# routed_anemo3.net
KiCad netlist of a schematic drawn in EAGLE
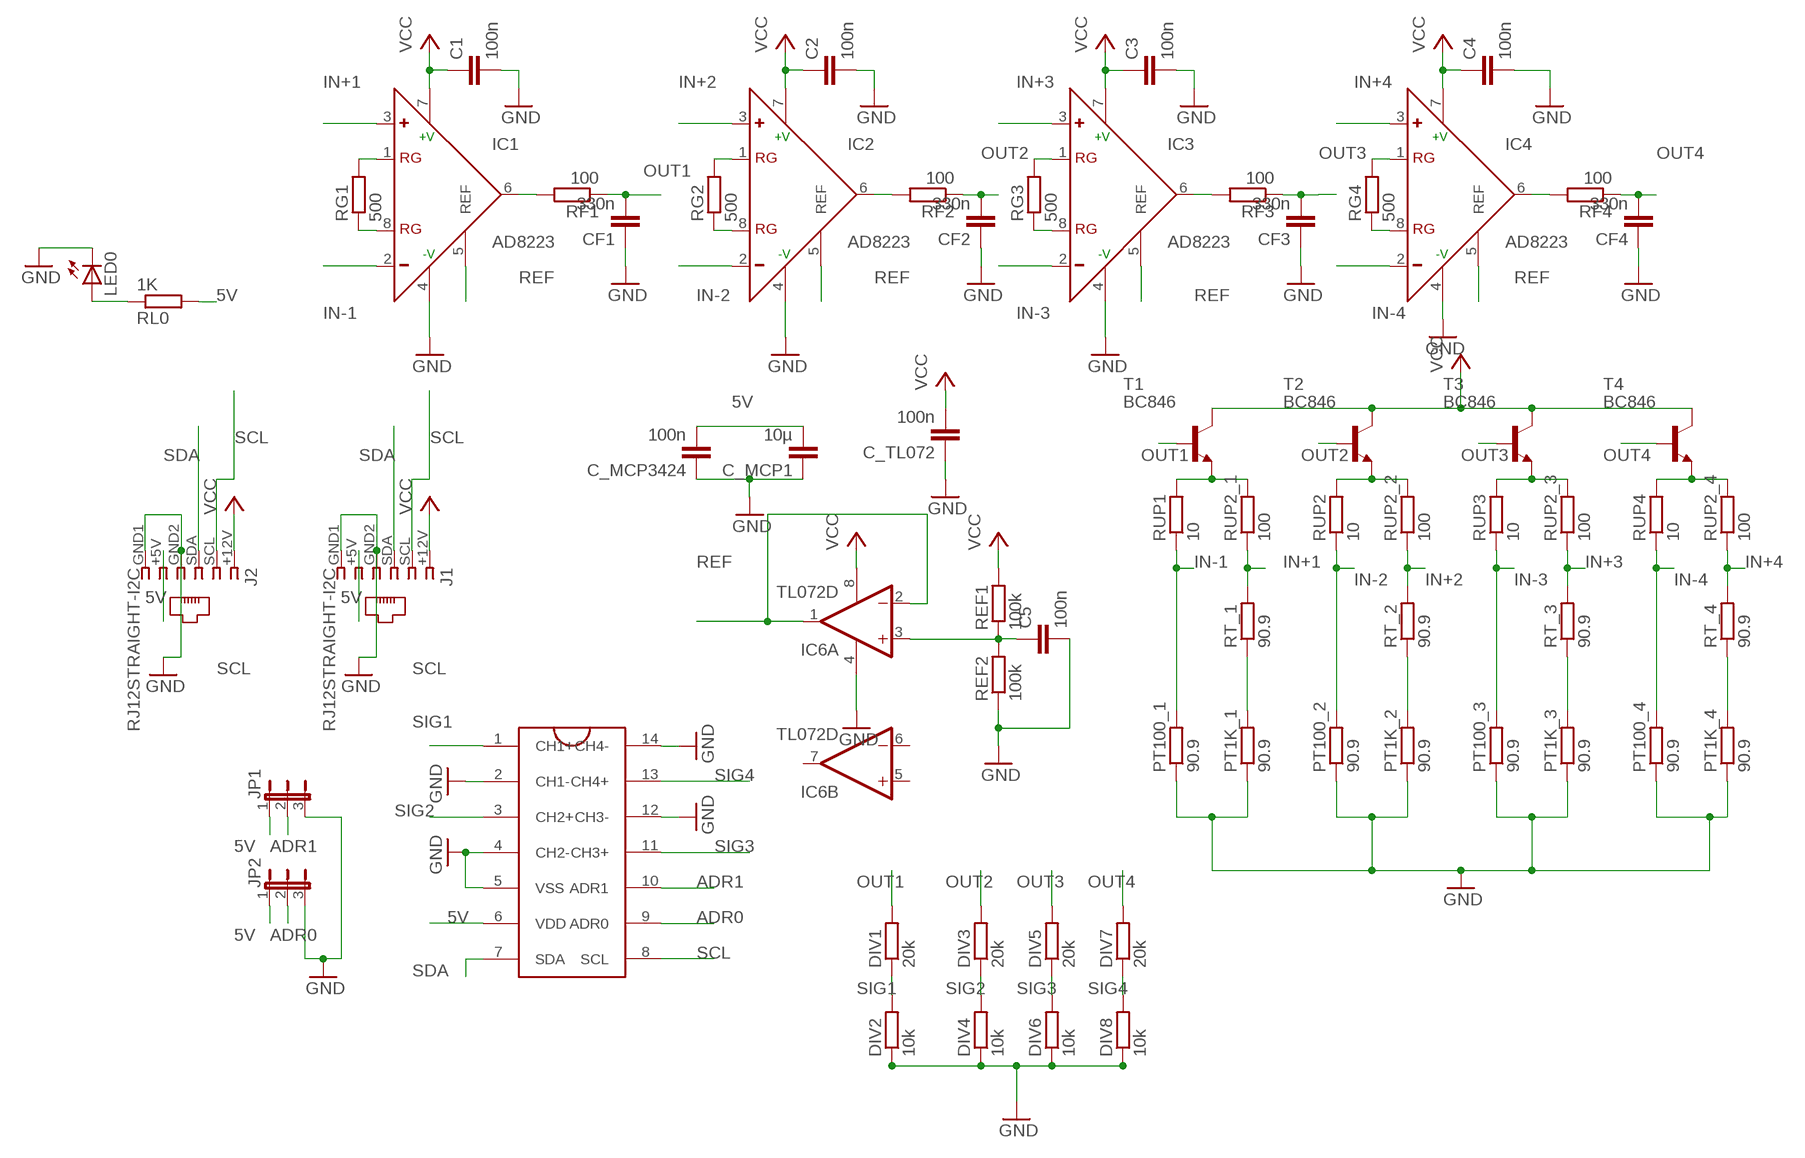
[diagram p0: schematic, sheet 1]

(export (version "E")
  (design (tool "Eeschema 10.0.6"))
  (components
    (comp (ref "C1")
      (value "100n")
      (footprint "eagle-import:C1206")
      (libsource (lib "eagle-import") (part "C-EUC1206"))
    )
    (comp (ref "C2")
      (value "100n")
      (footprint "eagle-import:C1206")
      (libsource (lib "eagle-import") (part "C-EUC1206"))
    )
    (comp (ref "C3")
      (value "100n")
      (footprint "eagle-import:C1206")
      (libsource (lib "eagle-import") (part "C-EUC1206"))
    )
    (comp (ref "C4")
      (value "100n")
      (footprint "eagle-import:C1206")
      (libsource (lib "eagle-import") (part "C-EUC1206"))
    )
    (comp (ref "C5")
      (value "100n")
      (footprint "eagle-import:C1206")
      (libsource (lib "eagle-import") (part "C-EUC1206"))
    )
    (comp (ref "CF1")
      (value "330n")
      (footprint "eagle-import:C1206")
      (libsource (lib "eagle-import") (part "C-EUC1206"))
    )
    (comp (ref "CF2")
      (value "330n")
      (footprint "eagle-import:C1206")
      (libsource (lib "eagle-import") (part "C-EUC1206"))
    )
    (comp (ref "CF3")
      (value "330n")
      (footprint "eagle-import:C1206")
      (libsource (lib "eagle-import") (part "C-EUC1206"))
    )
    (comp (ref "CF4")
      (value "330n")
      (footprint "eagle-import:C1206")
      (libsource (lib "eagle-import") (part "C-EUC1206"))
    )
    (comp (ref "C_MCP1")
      (value "10µ")
      (footprint "eagle-import:C1206")
      (libsource (lib "eagle-import") (part "C-EUC1206"))
    )
    (comp (ref "C_MCP3424")
      (value "100n")
      (footprint "eagle-import:C1206")
      (libsource (lib "eagle-import") (part "C-EUC1206"))
    )
    (comp (ref "C_TL072")
      (value "100n")
      (footprint "eagle-import:C1206")
      (libsource (lib "eagle-import") (part "C-EUC1206"))
    )
    (comp (ref "DIV1")
      (value "20k")
      (footprint "eagle-import:M1206")
      (libsource (lib "eagle-import") (part "R-EU_M1206"))
    )
    (comp (ref "DIV2")
      (value "10k")
      (footprint "eagle-import:M1206")
      (libsource (lib "eagle-import") (part "R-EU_M1206"))
    )
    (comp (ref "DIV3")
      (value "20k")
      (footprint "eagle-import:M1206")
      (libsource (lib "eagle-import") (part "R-EU_M1206"))
    )
    (comp (ref "DIV4")
      (value "10k")
      (footprint "eagle-import:M1206")
      (libsource (lib "eagle-import") (part "R-EU_M1206"))
    )
    (comp (ref "DIV5")
      (value "20k")
      (footprint "eagle-import:M1206")
      (libsource (lib "eagle-import") (part "R-EU_M1206"))
    )
    (comp (ref "DIV6")
      (value "10k")
      (footprint "eagle-import:M1206")
      (libsource (lib "eagle-import") (part "R-EU_M1206"))
    )
    (comp (ref "DIV7")
      (value "20k")
      (footprint "eagle-import:M1206")
      (libsource (lib "eagle-import") (part "R-EU_M1206"))
    )
    (comp (ref "DIV8")
      (value "10k")
      (footprint "eagle-import:M1206")
      (libsource (lib "eagle-import") (part "R-EU_M1206"))
    )
    (comp (ref "IC1")
      (value "AD8223")
      (footprint "eagle-import:SO8")
      (fields (field (name "MPN") "AD620AR"))
      (libsource (lib "eagle-import") (part "AD620R"))
    )
    (comp (ref "IC2")
      (value "AD8223")
      (footprint "eagle-import:SO8")
      (fields (field (name "MPN") "AD620AR"))
      (libsource (lib "eagle-import") (part "AD620R"))
    )
    (comp (ref "IC3")
      (value "AD8223")
      (footprint "eagle-import:SO8")
      (fields (field (name "MPN") "AD620AR"))
      (libsource (lib "eagle-import") (part "AD620R"))
    )
    (comp (ref "IC4")
      (value "AD8223")
      (footprint "eagle-import:SO8")
      (fields (field (name "MPN") "AD620AR"))
      (libsource (lib "eagle-import") (part "AD620R"))
    )
    (comp (ref "IC6")
      (value "TL072D")
      (footprint "eagle-import:SO08")
      (libsource (lib "eagle-import") (part "TL072D"))
    )
    (comp (ref "J1")
      (value "RJ12STRAIGHT-I2C")
      (footprint "eagle-import:RJ12-STRAIGHT-I2C")
      (libsource (lib "eagle-import") (part "RJ12STRAIGHT-I2C"))
    )
    (comp (ref "J2")
      (value "RJ12STRAIGHT-I2C")
      (footprint "eagle-import:RJ12-STRAIGHT-I2C")
      (libsource (lib "eagle-import") (part "RJ12STRAIGHT-I2C"))
    )
    (comp (ref "JP1")
      (value "JP2E")
      (footprint "eagle-import:JP2")
      (libsource (lib "eagle-import") (part "JP2E"))
    )
    (comp (ref "JP2")
      (value "JP2E")
      (footprint "eagle-import:JP2")
      (libsource (lib "eagle-import") (part "JP2E"))
    )
    (comp (ref "LED0")
      (value "LED1206")
      (footprint "eagle-import:LED-1206")
      (libsource (lib "eagle-import") (part "LED1206"))
    )
    (comp (ref "PT1K_1")
      (value "90.9")
      (footprint "eagle-import:M1206")
      (libsource (lib "eagle-import") (part "R-EU_M1206"))
    )
    (comp (ref "PT1K_2")
      (value "90.9")
      (footprint "eagle-import:M1206")
      (libsource (lib "eagle-import") (part "R-EU_M1206"))
    )
    (comp (ref "PT1K_3")
      (value "90.9")
      (footprint "eagle-import:M1206")
      (libsource (lib "eagle-import") (part "R-EU_M1206"))
    )
    (comp (ref "PT1K_4")
      (value "90.9")
      (footprint "eagle-import:M1206")
      (libsource (lib "eagle-import") (part "R-EU_M1206"))
    )
    (comp (ref "PT100_1")
      (value "90.9")
      (footprint "eagle-import:M1206")
      (libsource (lib "eagle-import") (part "R-EU_M1206"))
    )
    (comp (ref "PT100_2")
      (value "90.9")
      (footprint "eagle-import:M1206")
      (libsource (lib "eagle-import") (part "R-EU_M1206"))
    )
    (comp (ref "PT100_3")
      (value "90.9")
      (footprint "eagle-import:M1206")
      (libsource (lib "eagle-import") (part "R-EU_M1206"))
    )
    (comp (ref "PT100_4")
      (value "90.9")
      (footprint "eagle-import:M1206")
      (libsource (lib "eagle-import") (part "R-EU_M1206"))
    )
    (comp (ref "REF1")
      (value "100k")
      (footprint "eagle-import:M1206")
      (libsource (lib "eagle-import") (part "R-EU_M1206"))
    )
    (comp (ref "REF2")
      (value "100k")
      (footprint "eagle-import:M1206")
      (libsource (lib "eagle-import") (part "R-EU_M1206"))
    )
    (comp (ref "RF1")
      (value "100")
      (footprint "eagle-import:M1206")
      (libsource (lib "eagle-import") (part "R-EU_M1206"))
    )
    (comp (ref "RF2")
      (value "100")
      (footprint "eagle-import:M1206")
      (libsource (lib "eagle-import") (part "R-EU_M1206"))
    )
    (comp (ref "RF3")
      (value "100")
      (footprint "eagle-import:M1206")
      (libsource (lib "eagle-import") (part "R-EU_M1206"))
    )
    (comp (ref "RF4")
      (value "100")
      (footprint "eagle-import:M1206")
      (libsource (lib "eagle-import") (part "R-EU_M1206"))
    )
    (comp (ref "RG1")
      (value "500")
      (footprint "eagle-import:M1206")
      (libsource (lib "eagle-import") (part "R-EU_M1206"))
    )
    (comp (ref "RG2")
      (value "500")
      (footprint "eagle-import:M1206")
      (libsource (lib "eagle-import") (part "R-EU_M1206"))
    )
    (comp (ref "RG3")
      (value "500")
      (footprint "eagle-import:M1206")
      (libsource (lib "eagle-import") (part "R-EU_M1206"))
    )
    (comp (ref "RG4")
      (value "500")
      (footprint "eagle-import:M1206")
      (libsource (lib "eagle-import") (part "R-EU_M1206"))
    )
    (comp (ref "RL0")
      (value "1K")
      (footprint "eagle-import:M1206")
      (libsource (lib "eagle-import") (part "R-EU_M1206"))
    )
    (comp (ref "RT_1")
      (value "90.9")
      (footprint "eagle-import:M1206")
      (libsource (lib "eagle-import") (part "R-EU_M1206"))
    )
    (comp (ref "RT_2")
      (value "90.9")
      (footprint "eagle-import:M1206")
      (libsource (lib "eagle-import") (part "R-EU_M1206"))
    )
    (comp (ref "RT_3")
      (value "90.9")
      (footprint "eagle-import:M1206")
      (libsource (lib "eagle-import") (part "R-EU_M1206"))
    )
    (comp (ref "RT_4")
      (value "90.9")
      (footprint "eagle-import:M1206")
      (libsource (lib "eagle-import") (part "R-EU_M1206"))
    )
    (comp (ref "RUP1")
      (value "10")
      (footprint "eagle-import:M1206")
      (libsource (lib "eagle-import") (part "R-EU_M1206"))
    )
    (comp (ref "RUP2")
      (value "10")
      (footprint "eagle-import:M1206")
      (libsource (lib "eagle-import") (part "R-EU_M1206"))
    )
    (comp (ref "RUP2_1")
      (value "100")
      (footprint "eagle-import:M1206")
      (libsource (lib "eagle-import") (part "R-EU_M1206"))
    )
    (comp (ref "RUP2_2")
      (value "100")
      (footprint "eagle-import:M1206")
      (libsource (lib "eagle-import") (part "R-EU_M1206"))
    )
    (comp (ref "RUP2_3")
      (value "100")
      (footprint "eagle-import:M1206")
      (libsource (lib "eagle-import") (part "R-EU_M1206"))
    )
    (comp (ref "RUP2_4")
      (value "100")
      (footprint "eagle-import:M1206")
      (libsource (lib "eagle-import") (part "R-EU_M1206"))
    )
    (comp (ref "RUP3")
      (value "10")
      (footprint "eagle-import:M1206")
      (libsource (lib "eagle-import") (part "R-EU_M1206"))
    )
    (comp (ref "RUP4")
      (value "10")
      (footprint "eagle-import:M1206")
      (libsource (lib "eagle-import") (part "R-EU_M1206"))
    )
    (comp (ref "T1")
      (value "BC846")
      (footprint "eagle-import:SOT23")
      (libsource (lib "eagle-import") (part "BC846"))
    )
    (comp (ref "T2")
      (value "BC846")
      (footprint "eagle-import:SOT23")
      (libsource (lib "eagle-import") (part "BC846"))
    )
    (comp (ref "T3")
      (value "BC846")
      (footprint "eagle-import:SOT23")
      (libsource (lib "eagle-import") (part "BC846"))
    )
    (comp (ref "T4")
      (value "BC846")
      (footprint "eagle-import:SOT23")
      (libsource (lib "eagle-import") (part "BC846"))
    )
    (comp (ref "U$1")
      (value "MCP3424(SO14)")
      (footprint "eagle-import:14LDSOIC")
      (libsource (lib "eagle-import") (part "MCP3424(SO14)"))
    )
  )
  (nets
    (net (code "1") (name "/5V") (class "Default")
      (node (ref "C_MCP1") (pin "2") (pinfunction "2_2") (pintype "passive"))
      (node (ref "C_MCP3424") (pin "2") (pinfunction "2_2") (pintype "passive"))
      (node (ref "J1") (pin "+5V") (pinfunction "5_+5V") (pintype "bidirectional"))
      (node (ref "J2") (pin "+5V") (pinfunction "5_+5V") (pintype "bidirectional"))
      (node (ref "JP1") (pin "1") (pinfunction "1_1") (pintype "passive"))
      (node (ref "JP2") (pin "1") (pinfunction "1_1") (pintype "passive"))
      (node (ref "RL0") (pin "2") (pinfunction "2_2") (pintype "passive"))
      (node (ref "U$1") (pin "6") (pinfunction "VDD_6") (pintype "bidirectional"))
    )
    (net (code "2") (name "/ADR0") (class "Default")
      (node (ref "JP2") (pin "2") (pinfunction "2_2") (pintype "passive"))
      (node (ref "U$1") (pin "9") (pinfunction "ADR0_9") (pintype "bidirectional"))
    )
    (net (code "3") (name "/ADR1") (class "Default")
      (node (ref "JP1") (pin "2") (pinfunction "2_2") (pintype "passive"))
      (node (ref "U$1") (pin "10") (pinfunction "ADR1_10") (pintype "bidirectional"))
    )
    (net (code "4") (name "/IN+1") (class "Default")
      (node (ref "IC1") (pin "3") (pinfunction "+_3") (pintype "input"))
      (node (ref "RT_1") (pin "2") (pinfunction "2_2") (pintype "passive"))
      (node (ref "RUP2_1") (pin "1") (pinfunction "1_1") (pintype "passive"))
    )
    (net (code "5") (name "/IN+2") (class "Default")
      (node (ref "IC2") (pin "3") (pinfunction "+_3") (pintype "input"))
      (node (ref "RT_2") (pin "2") (pinfunction "2_2") (pintype "passive"))
      (node (ref "RUP2_2") (pin "1") (pinfunction "1_1") (pintype "passive"))
    )
    (net (code "6") (name "/IN+3") (class "Default")
      (node (ref "IC3") (pin "3") (pinfunction "+_3") (pintype "input"))
      (node (ref "RT_3") (pin "2") (pinfunction "2_2") (pintype "passive"))
      (node (ref "RUP2_3") (pin "1") (pinfunction "1_1") (pintype "passive"))
    )
    (net (code "7") (name "/IN+4") (class "Default")
      (node (ref "IC4") (pin "3") (pinfunction "+_3") (pintype "input"))
      (node (ref "RT_4") (pin "2") (pinfunction "2_2") (pintype "passive"))
      (node (ref "RUP2_4") (pin "1") (pinfunction "1_1") (pintype "passive"))
    )
    (net (code "8") (name "/IN-1") (class "Default")
      (node (ref "IC1") (pin "2") (pinfunction "-_2") (pintype "input"))
      (node (ref "PT100_1") (pin "2") (pinfunction "2_2") (pintype "passive"))
      (node (ref "RUP1") (pin "1") (pinfunction "1_1") (pintype "passive"))
    )
    (net (code "9") (name "/IN-2") (class "Default")
      (node (ref "IC2") (pin "2") (pinfunction "-_2") (pintype "input"))
      (node (ref "PT100_2") (pin "2") (pinfunction "2_2") (pintype "passive"))
      (node (ref "RUP2") (pin "1") (pinfunction "1_1") (pintype "passive"))
    )
    (net (code "10") (name "/IN-3") (class "Default")
      (node (ref "IC3") (pin "2") (pinfunction "-_2") (pintype "input"))
      (node (ref "PT100_3") (pin "2") (pinfunction "2_2") (pintype "passive"))
      (node (ref "RUP3") (pin "1") (pinfunction "1_1") (pintype "passive"))
    )
    (net (code "11") (name "/IN-4") (class "Default")
      (node (ref "IC4") (pin "2") (pinfunction "-_2") (pintype "input"))
      (node (ref "PT100_4") (pin "2") (pinfunction "2_2") (pintype "passive"))
      (node (ref "RUP4") (pin "1") (pinfunction "1_1") (pintype "passive"))
    )
    (net (code "12") (name "/OUT1") (class "Default")
      (node (ref "CF1") (pin "2") (pinfunction "2_2") (pintype "passive"))
      (node (ref "DIV1") (pin "2") (pinfunction "2_2") (pintype "passive"))
      (node (ref "RF1") (pin "1") (pinfunction "1_1") (pintype "passive"))
      (node (ref "T1") (pin "1") (pinfunction "B_1") (pintype "passive"))
    )
    (net (code "13") (name "/OUT2") (class "Default")
      (node (ref "CF2") (pin "2") (pinfunction "2_2") (pintype "passive"))
      (node (ref "DIV3") (pin "2") (pinfunction "2_2") (pintype "passive"))
      (node (ref "RF2") (pin "1") (pinfunction "1_1") (pintype "passive"))
      (node (ref "T2") (pin "1") (pinfunction "B_1") (pintype "passive"))
    )
    (net (code "14") (name "/OUT3") (class "Default")
      (node (ref "CF3") (pin "2") (pinfunction "2_2") (pintype "passive"))
      (node (ref "DIV5") (pin "2") (pinfunction "2_2") (pintype "passive"))
      (node (ref "RF3") (pin "1") (pinfunction "1_1") (pintype "passive"))
      (node (ref "T3") (pin "1") (pinfunction "B_1") (pintype "passive"))
    )
    (net (code "15") (name "/OUT4") (class "Default")
      (node (ref "CF4") (pin "2") (pinfunction "2_2") (pintype "passive"))
      (node (ref "DIV7") (pin "2") (pinfunction "2_2") (pintype "passive"))
      (node (ref "RF4") (pin "1") (pinfunction "1_1") (pintype "passive"))
      (node (ref "T4") (pin "1") (pinfunction "B_1") (pintype "passive"))
    )
    (net (code "16") (name "/REF") (class "Default")
      (node (ref "IC1") (pin "5") (pinfunction "REF_5") (pintype "passive"))
      (node (ref "IC2") (pin "5") (pinfunction "REF_5") (pintype "passive"))
      (node (ref "IC3") (pin "5") (pinfunction "REF_5") (pintype "passive"))
      (node (ref "IC4") (pin "5") (pinfunction "REF_5") (pintype "passive"))
      (node (ref "IC6") (pin "1") (pinfunction "OUT_1") (pintype "output"))
      (node (ref "IC6") (pin "2") (pinfunction "-IN_2") (pintype "input"))
    )
    (net (code "17") (name "/SCL") (class "Default")
      (node (ref "J1") (pin "SCL") (pinfunction "2_SCL") (pintype "bidirectional"))
      (node (ref "J2") (pin "SCL") (pinfunction "2_SCL") (pintype "bidirectional"))
      (node (ref "U$1") (pin "8") (pinfunction "SCL_8") (pintype "bidirectional"))
    )
    (net (code "18") (name "/SDA") (class "Default")
      (node (ref "J1") (pin "SDA") (pinfunction "3_SDA") (pintype "bidirectional"))
      (node (ref "J2") (pin "SDA") (pinfunction "3_SDA") (pintype "bidirectional"))
      (node (ref "U$1") (pin "7") (pinfunction "SDA_7") (pintype "bidirectional"))
    )
    (net (code "19") (name "/SIG1") (class "Default")
      (node (ref "DIV1") (pin "1") (pinfunction "1_1") (pintype "passive"))
      (node (ref "DIV2") (pin "2") (pinfunction "2_2") (pintype "passive"))
      (node (ref "U$1") (pin "1") (pinfunction "CH1+_1") (pintype "bidirectional"))
    )
    (net (code "20") (name "/SIG2") (class "Default")
      (node (ref "DIV3") (pin "1") (pinfunction "1_1") (pintype "passive"))
      (node (ref "DIV4") (pin "2") (pinfunction "2_2") (pintype "passive"))
      (node (ref "U$1") (pin "3") (pinfunction "CH2+_3") (pintype "bidirectional"))
    )
    (net (code "21") (name "/SIG3") (class "Default")
      (node (ref "DIV5") (pin "1") (pinfunction "1_1") (pintype "passive"))
      (node (ref "DIV6") (pin "2") (pinfunction "2_2") (pintype "passive"))
      (node (ref "U$1") (pin "11") (pinfunction "CH3+_11") (pintype "bidirectional"))
    )
    (net (code "22") (name "/SIG4") (class "Default")
      (node (ref "DIV7") (pin "1") (pinfunction "1_1") (pintype "passive"))
      (node (ref "DIV8") (pin "2") (pinfunction "2_2") (pintype "passive"))
      (node (ref "U$1") (pin "13") (pinfunction "CH4+_13") (pintype "bidirectional"))
    )
    (net (code "23") (name "GND") (class "Default")
      (node (ref "C1") (pin "2") (pinfunction "2_2") (pintype "passive"))
      (node (ref "C2") (pin "2") (pinfunction "2_2") (pintype "passive"))
      (node (ref "C3") (pin "2") (pinfunction "2_2") (pintype "passive"))
      (node (ref "C4") (pin "2") (pinfunction "2_2") (pintype "passive"))
      (node (ref "C5") (pin "2") (pinfunction "2_2") (pintype "passive"))
      (node (ref "CF1") (pin "1") (pinfunction "1_1") (pintype "passive"))
      (node (ref "CF2") (pin "1") (pinfunction "1_1") (pintype "passive"))
      (node (ref "CF3") (pin "1") (pinfunction "1_1") (pintype "passive"))
      (node (ref "CF4") (pin "1") (pinfunction "1_1") (pintype "passive"))
      (node (ref "C_MCP1") (pin "1") (pinfunction "1_1") (pintype "passive"))
      (node (ref "C_MCP3424") (pin "1") (pinfunction "1_1") (pintype "passive"))
      (node (ref "C_TL072") (pin "1") (pinfunction "1_1") (pintype "passive"))
      (node (ref "DIV2") (pin "1") (pinfunction "1_1") (pintype "passive"))
      (node (ref "DIV4") (pin "1") (pinfunction "1_1") (pintype "passive"))
      (node (ref "DIV6") (pin "1") (pinfunction "1_1") (pintype "passive"))
      (node (ref "DIV8") (pin "1") (pinfunction "1_1") (pintype "passive"))
      (node (ref "IC1") (pin "4") (pinfunction "-V_4") (pintype "power_in"))
      (node (ref "IC2") (pin "4") (pinfunction "-V_4") (pintype "power_in"))
      (node (ref "IC3") (pin "4") (pinfunction "-V_4") (pintype "power_in"))
      (node (ref "IC4") (pin "4") (pinfunction "-V_4") (pintype "power_in"))
      (node (ref "IC6") (pin "4") (pinfunction "V-_4") (pintype "power_in"))
      (node (ref "J1") (pin "GND1") (pinfunction "6_GND1") (pintype "bidirectional"))
      (node (ref "J1") (pin "GND2") (pinfunction "4_GND2") (pintype "bidirectional"))
      (node (ref "J2") (pin "GND1") (pinfunction "6_GND1") (pintype "bidirectional"))
      (node (ref "J2") (pin "GND2") (pinfunction "4_GND2") (pintype "bidirectional"))
      (node (ref "JP1") (pin "3") (pinfunction "3_3") (pintype "passive"))
      (node (ref "JP2") (pin "3") (pinfunction "3_3") (pintype "passive"))
      (node (ref "LED0") (pin "C") (pinfunction "C_C") (pintype "passive"))
      (node (ref "PT100_1") (pin "1") (pinfunction "1_1") (pintype "passive"))
      (node (ref "PT100_2") (pin "1") (pinfunction "1_1") (pintype "passive"))
      (node (ref "PT100_3") (pin "1") (pinfunction "1_1") (pintype "passive"))
      (node (ref "PT100_4") (pin "1") (pinfunction "1_1") (pintype "passive"))
      (node (ref "PT1K_1") (pin "1") (pinfunction "1_1") (pintype "passive"))
      (node (ref "PT1K_2") (pin "1") (pinfunction "1_1") (pintype "passive"))
      (node (ref "PT1K_3") (pin "1") (pinfunction "1_1") (pintype "passive"))
      (node (ref "PT1K_4") (pin "1") (pinfunction "1_1") (pintype "passive"))
      (node (ref "REF2") (pin "1") (pinfunction "1_1") (pintype "passive"))
      (node (ref "U$1") (pin "12") (pinfunction "CH3-_12") (pintype "bidirectional"))
      (node (ref "U$1") (pin "14") (pinfunction "CH4-_14") (pintype "bidirectional"))
      (node (ref "U$1") (pin "2") (pinfunction "CH1-_2") (pintype "bidirectional"))
      (node (ref "U$1") (pin "4") (pinfunction "CH2-_4") (pintype "bidirectional"))
      (node (ref "U$1") (pin "5") (pinfunction "VSS_5") (pintype "bidirectional"))
    )
    (net (code "24") (name "Net-(IC1-OUT)") (class "Default")
      (node (ref "IC1") (pin "6") (pinfunction "OUT_6") (pintype "output"))
      (node (ref "RF1") (pin "2") (pinfunction "2_2") (pintype "passive"))
    )
    (net (code "25") (name "Net-(IC1-RG-Pad1)") (class "Default")
      (node (ref "IC1") (pin "1") (pinfunction "RG_1") (pintype "passive"))
      (node (ref "RG1") (pin "2") (pinfunction "2_2") (pintype "passive"))
    )
    (net (code "26") (name "Net-(IC1-RG-Pad8)") (class "Default")
      (node (ref "IC1") (pin "8") (pinfunction "RG_8") (pintype "passive"))
      (node (ref "RG1") (pin "1") (pinfunction "1_1") (pintype "passive"))
    )
    (net (code "27") (name "Net-(IC2-OUT)") (class "Default")
      (node (ref "IC2") (pin "6") (pinfunction "OUT_6") (pintype "output"))
      (node (ref "RF2") (pin "2") (pinfunction "2_2") (pintype "passive"))
    )
    (net (code "28") (name "Net-(IC2-RG-Pad1)") (class "Default")
      (node (ref "IC2") (pin "1") (pinfunction "RG_1") (pintype "passive"))
      (node (ref "RG2") (pin "2") (pinfunction "2_2") (pintype "passive"))
    )
    (net (code "29") (name "Net-(IC2-RG-Pad8)") (class "Default")
      (node (ref "IC2") (pin "8") (pinfunction "RG_8") (pintype "passive"))
      (node (ref "RG2") (pin "1") (pinfunction "1_1") (pintype "passive"))
    )
    (net (code "30") (name "Net-(IC3-OUT)") (class "Default")
      (node (ref "IC3") (pin "6") (pinfunction "OUT_6") (pintype "output"))
      (node (ref "RF3") (pin "2") (pinfunction "2_2") (pintype "passive"))
    )
    (net (code "31") (name "Net-(IC3-RG-Pad1)") (class "Default")
      (node (ref "IC3") (pin "1") (pinfunction "RG_1") (pintype "passive"))
      (node (ref "RG3") (pin "2") (pinfunction "2_2") (pintype "passive"))
    )
    (net (code "32") (name "Net-(IC3-RG-Pad8)") (class "Default")
      (node (ref "IC3") (pin "8") (pinfunction "RG_8") (pintype "passive"))
      (node (ref "RG3") (pin "1") (pinfunction "1_1") (pintype "passive"))
    )
    (net (code "33") (name "Net-(IC4-OUT)") (class "Default")
      (node (ref "IC4") (pin "6") (pinfunction "OUT_6") (pintype "output"))
      (node (ref "RF4") (pin "2") (pinfunction "2_2") (pintype "passive"))
    )
    (net (code "34") (name "Net-(IC4-RG-Pad1)") (class "Default")
      (node (ref "IC4") (pin "1") (pinfunction "RG_1") (pintype "passive"))
      (node (ref "RG4") (pin "2") (pinfunction "2_2") (pintype "passive"))
    )
    (net (code "35") (name "Net-(IC4-RG-Pad8)") (class "Default")
      (node (ref "IC4") (pin "8") (pinfunction "RG_8") (pintype "passive"))
      (node (ref "RG4") (pin "1") (pinfunction "1_1") (pintype "passive"))
    )
    (net (code "36") (name "Net-(IC6A-+IN)") (class "Default")
      (node (ref "C5") (pin "1") (pinfunction "1_1") (pintype "passive"))
      (node (ref "IC6") (pin "3") (pinfunction "+IN_3") (pintype "input"))
      (node (ref "REF1") (pin "1") (pinfunction "1_1") (pintype "passive"))
      (node (ref "REF2") (pin "2") (pinfunction "2_2") (pintype "passive"))
    )
    (net (code "37") (name "Net-(LED0-PadA)") (class "Default")
      (node (ref "LED0") (pin "A") (pinfunction "A_A") (pintype "passive"))
      (node (ref "RL0") (pin "1") (pinfunction "1_1") (pintype "passive"))
    )
    (net (code "38") (name "Net-(PT1K_1-Pad2)") (class "Default")
      (node (ref "PT1K_1") (pin "2") (pinfunction "2_2") (pintype "passive"))
      (node (ref "RT_1") (pin "1") (pinfunction "1_1") (pintype "passive"))
    )
    (net (code "39") (name "Net-(PT1K_2-Pad2)") (class "Default")
      (node (ref "PT1K_2") (pin "2") (pinfunction "2_2") (pintype "passive"))
      (node (ref "RT_2") (pin "1") (pinfunction "1_1") (pintype "passive"))
    )
    (net (code "40") (name "Net-(PT1K_3-Pad2)") (class "Default")
      (node (ref "PT1K_3") (pin "2") (pinfunction "2_2") (pintype "passive"))
      (node (ref "RT_3") (pin "1") (pinfunction "1_1") (pintype "passive"))
    )
    (net (code "41") (name "Net-(PT1K_4-Pad2)") (class "Default")
      (node (ref "PT1K_4") (pin "2") (pinfunction "2_2") (pintype "passive"))
      (node (ref "RT_4") (pin "1") (pinfunction "1_1") (pintype "passive"))
    )
    (net (code "42") (name "Net-(T1-E)") (class "Default")
      (node (ref "RUP1") (pin "2") (pinfunction "2_2") (pintype "passive"))
      (node (ref "RUP2_1") (pin "2") (pinfunction "2_2") (pintype "passive"))
      (node (ref "T1") (pin "2") (pinfunction "E_2") (pintype "passive"))
    )
    (net (code "43") (name "Net-(T2-E)") (class "Default")
      (node (ref "RUP2") (pin "2") (pinfunction "2_2") (pintype "passive"))
      (node (ref "RUP2_2") (pin "2") (pinfunction "2_2") (pintype "passive"))
      (node (ref "T2") (pin "2") (pinfunction "E_2") (pintype "passive"))
    )
    (net (code "44") (name "Net-(T3-E)") (class "Default")
      (node (ref "RUP2_3") (pin "2") (pinfunction "2_2") (pintype "passive"))
      (node (ref "RUP3") (pin "2") (pinfunction "2_2") (pintype "passive"))
      (node (ref "T3") (pin "2") (pinfunction "E_2") (pintype "passive"))
    )
    (net (code "45") (name "Net-(T4-E)") (class "Default")
      (node (ref "RUP2_4") (pin "2") (pinfunction "2_2") (pintype "passive"))
      (node (ref "RUP4") (pin "2") (pinfunction "2_2") (pintype "passive"))
      (node (ref "T4") (pin "2") (pinfunction "E_2") (pintype "passive"))
    )
    (net (code "46") (name "VCC") (class "Default")
      (node (ref "C1") (pin "1") (pinfunction "1_1") (pintype "passive"))
      (node (ref "C2") (pin "1") (pinfunction "1_1") (pintype "passive"))
      (node (ref "C3") (pin "1") (pinfunction "1_1") (pintype "passive"))
      (node (ref "C4") (pin "1") (pinfunction "1_1") (pintype "passive"))
      (node (ref "C_TL072") (pin "2") (pinfunction "2_2") (pintype "passive"))
      (node (ref "IC1") (pin "7") (pinfunction "+V_7") (pintype "power_in"))
      (node (ref "IC2") (pin "7") (pinfunction "+V_7") (pintype "power_in"))
      (node (ref "IC3") (pin "7") (pinfunction "+V_7") (pintype "power_in"))
      (node (ref "IC4") (pin "7") (pinfunction "+V_7") (pintype "power_in"))
      (node (ref "IC6") (pin "8") (pinfunction "V+_8") (pintype "power_in"))
      (node (ref "J1") (pin "+12V") (pinfunction "1_+12V") (pintype "bidirectional"))
      (node (ref "J2") (pin "+12V") (pinfunction "1_+12V") (pintype "bidirectional"))
      (node (ref "REF1") (pin "2") (pinfunction "2_2") (pintype "passive"))
      (node (ref "T1") (pin "3") (pinfunction "C_3") (pintype "passive"))
      (node (ref "T2") (pin "3") (pinfunction "C_3") (pintype "passive"))
      (node (ref "T3") (pin "3") (pinfunction "C_3") (pintype "passive"))
      (node (ref "T4") (pin "3") (pinfunction "C_3") (pintype "passive"))
    )
    (net (code "47") (name "unconnected-(IC6B-+IN-Pad5)") (class "Default")
      (node (ref "IC6") (pin "5") (pinfunction "+IN_5") (pintype "input"))
    )
    (net (code "48") (name "unconnected-(IC6B--IN-Pad6)") (class "Default")
      (node (ref "IC6") (pin "6") (pinfunction "-IN_6") (pintype "input"))
    )
    (net (code "49") (name "unconnected-(IC6B-OUT-Pad7)") (class "Default")
      (node (ref "IC6") (pin "7") (pinfunction "OUT_7") (pintype "output"))
    )
  )
)
